# MHR15-inverter_current_sensors_v0.net
KiCad netlist of a schematic drawn in EAGLE
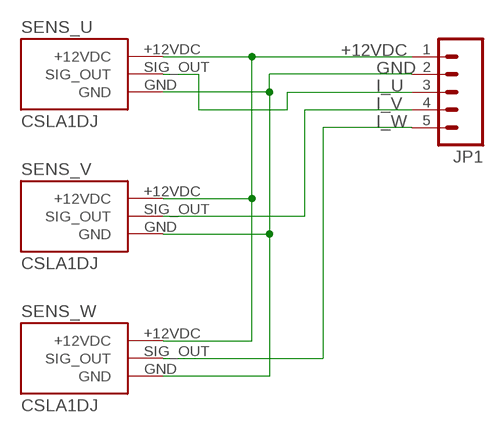
[diagram p0: schematic, sheet 1]

(export (version "E")
  (design (tool "Eeschema 10.0.6"))
  (components
    (comp (ref "JP1")
      (value "M05LOCK")
      (footprint "eagle-import:1X05_LOCK")
      (libsource (lib "eagle-import") (part "M05LOCK"))
    )
    (comp (ref "SENS_U")
      (value "CSLA1DJ")
      (footprint "eagle-import:CSLA1DJ")
      (libsource (lib "eagle-import") (part "CSLA1DJ"))
    )
    (comp (ref "SENS_V")
      (value "CSLA1DJ")
      (footprint "eagle-import:CSLA1DJ")
      (libsource (lib "eagle-import") (part "CSLA1DJ"))
    )
    (comp (ref "SENS_W")
      (value "CSLA1DJ")
      (footprint "eagle-import:CSLA1DJ")
      (libsource (lib "eagle-import") (part "CSLA1DJ"))
    )
  )
  (nets
    (net (code "1") (name "/+12VDC") (class "Default")
      (node (ref "JP1") (pin "1") (pinfunction "1_1") (pintype "passive"))
      (node (ref "SENS_U") (pin "+12VDC") (pinfunction "+12VDC_+12VDC") (pintype "bidirectional"))
      (node (ref "SENS_V") (pin "+12VDC") (pinfunction "+12VDC_+12VDC") (pintype "bidirectional"))
      (node (ref "SENS_W") (pin "+12VDC") (pinfunction "+12VDC_+12VDC") (pintype "bidirectional"))
    )
    (net (code "2") (name "/GND") (class "Default")
      (node (ref "JP1") (pin "2") (pinfunction "2_2") (pintype "passive"))
      (node (ref "SENS_U") (pin "GND") (pinfunction "GND_GND") (pintype "bidirectional"))
      (node (ref "SENS_V") (pin "GND") (pinfunction "GND_GND") (pintype "bidirectional"))
      (node (ref "SENS_W") (pin "GND") (pinfunction "GND_GND") (pintype "bidirectional"))
    )
    (net (code "3") (name "/I_U") (class "Default")
      (node (ref "JP1") (pin "3") (pinfunction "3_3") (pintype "passive"))
      (node (ref "SENS_U") (pin "SIG_OUT") (pinfunction "SIG_OUT_SIG_OUT") (pintype "bidirectional"))
    )
    (net (code "4") (name "/I_V") (class "Default")
      (node (ref "JP1") (pin "4") (pinfunction "4_4") (pintype "passive"))
      (node (ref "SENS_V") (pin "SIG_OUT") (pinfunction "SIG_OUT_SIG_OUT") (pintype "bidirectional"))
    )
    (net (code "5") (name "/I_W") (class "Default")
      (node (ref "JP1") (pin "5") (pinfunction "5_5") (pintype "passive"))
      (node (ref "SENS_W") (pin "SIG_OUT") (pinfunction "SIG_OUT_SIG_OUT") (pintype "bidirectional"))
    )
  )
)
